# Power.net
KiCad netlist of a schematic drawn in Altium Designer
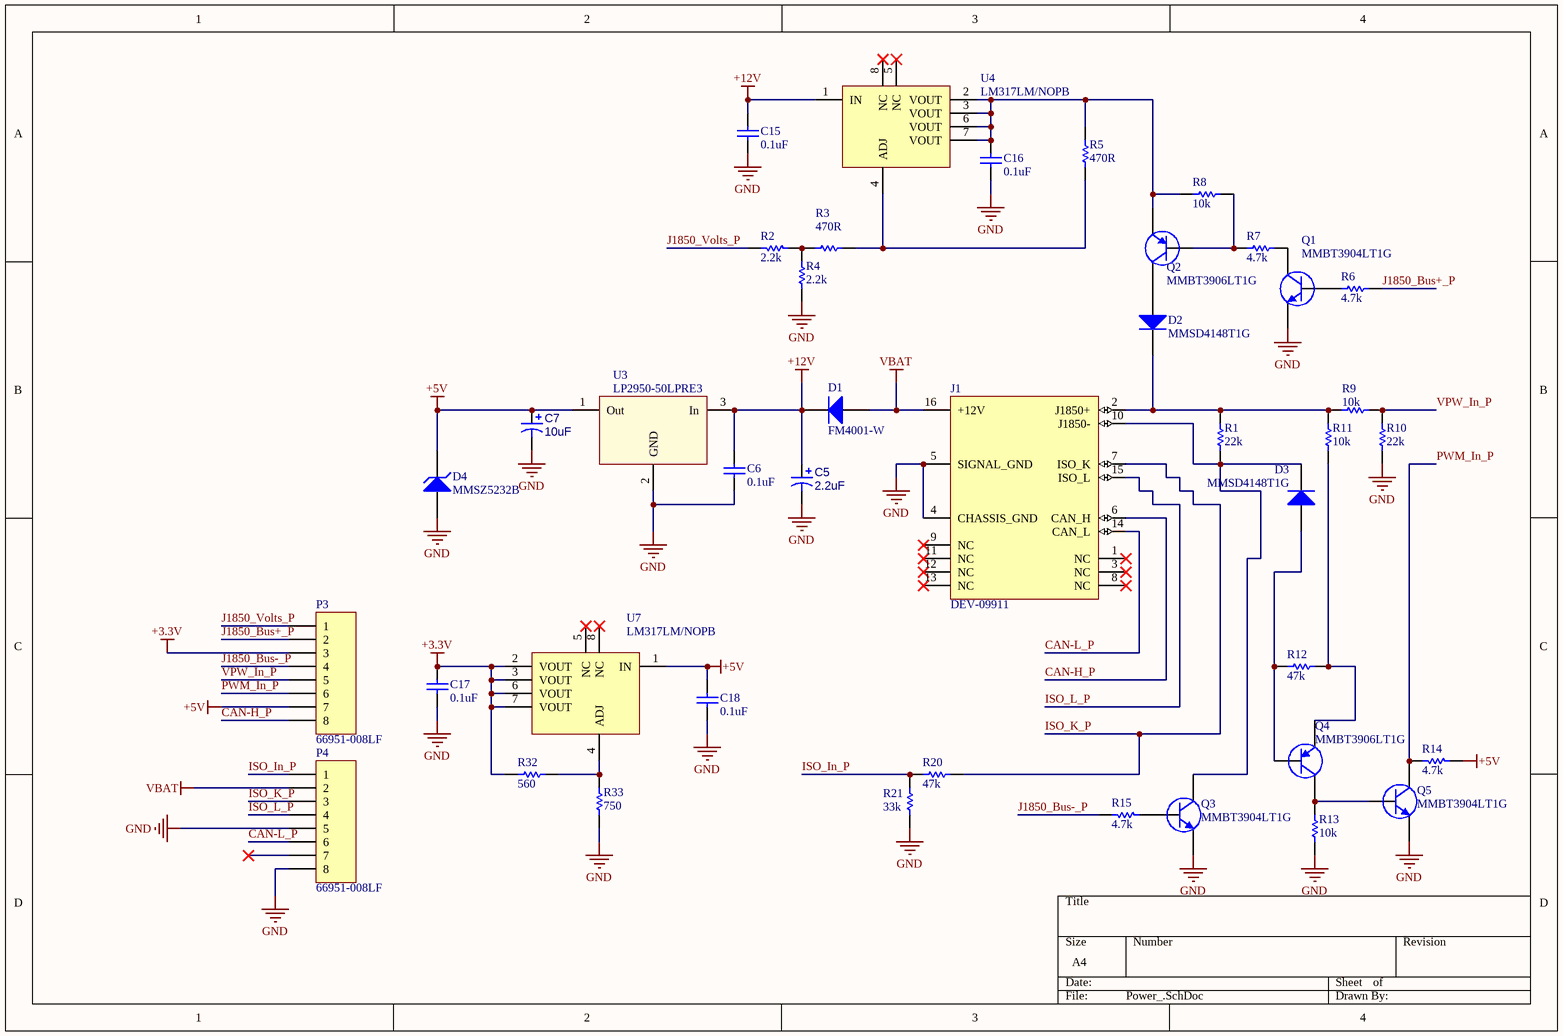
[diagram p0: Power_.SchDoc]

(export (version "E")
  (design (tool "Eeschema 10.0.6"))
  (components
    (comp (ref "C5")
      (value "2.2uF")
      (footprint "Panasonic_Ñ")
      (description "CAP ELECT 2.2UF SV 50V SMD")
      (fields (field (name "MANUFACTURER") "Panasonic") (field (name "PARTNUMBER") "EEE-1HA2R2NR"))
      (libsource (lib "OBDII-components") (part "EEE-1HA2R2NR"))
    )
    (comp (ref "C6")
      (value "0.1uF")
      (footprint "1608[0603]")
      (description "Surface-Mount Ceramic Multilayer Capacitor, 0.1uF, 10% Tolerance, 0603 Size, 50V")
      (libsource (lib "OBDII-components") (part "C0603C104K5RACTU"))
    )
    (comp (ref "C7")
      (value "10uF")
      (footprint "Panasonic_B")
      (description "CAP ELECT 10UF SV 10V SMD")
      (fields (field (name "MANUFACTURER") "Panasonic") (field (name "PARTNUMBER") "EEE-1AA100NR"))
      (libsource (lib "OBDII-components") (part "EEE-1AA100NR"))
    )
    (comp (ref "C15")
      (value "0.1uF")
      (footprint "1608[0603]")
      (description "Surface-Mount Ceramic Multilayer Capacitor, 0.1uF, X7R, 10% Tolerance, 0603 Size, 25V")
      (fields (field (name "PUBLISHER") "Altium Limited"))
      (libsource (lib "OBDII-components") (part "CGA3E2X7R1E104K080AA"))
    )
    (comp (ref "C16")
      (value "0.1uF")
      (footprint "1608[0603]")
      (description "Surface-Mount Ceramic Multilayer Capacitor, 0.1uF, X7R, 10% Tolerance, 0603 Size, 25V")
      (fields (field (name "PUBLISHER") "Altium Limited"))
      (libsource (lib "OBDII-components") (part "CGA3E2X7R1E104K080AA"))
    )
    (comp (ref "C17")
      (value "0.1uF")
      (footprint "1608[0603]")
      (description "Surface-Mount Ceramic Multilayer Capacitor, 0.1uF, 10% Tolerance, 0603 Size, 50V")
      (libsource (lib "OBDII-components") (part "C0603C104K5RACTU"))
    )
    (comp (ref "C18")
      (value "0.1uF")
      (footprint "1608[0603]")
      (description "Surface-Mount Ceramic Multilayer Capacitor, 0.1uF, 10% Tolerance, 0603 Size, 50V")
      (libsource (lib "OBDII-components") (part "C0603C104K5RACTU"))
    )
    (comp (ref "D1")
      (value "FM4001-W")
      (footprint "SMA,2.8mm")
      (description "1 Amp 50V  Rectifier")
      (libsource (lib "OBDII-components") (part "FM4001-W"))
    )
    (comp (ref "D2")
      (value "MMSD4148T1G")
      (footprint "SOD123")
      (description "High Conductance Fast Diode")
      (fields
        (field (name "MANUFACTURER") "OnSemi")
        (field (name "PUBLISHER") "Vanteon")
        (field (name "APPROVED") "M. Jablonski")
      )
      (libsource (lib "OBDII-components") (part "MMSD4148T1G"))
    )
    (comp (ref "D3")
      (value "MMSD4148T1G")
      (footprint "SOD123")
      (description "High Conductance Fast Diode")
      (fields
        (field (name "MANUFACTURER") "OnSemi")
        (field (name "PUBLISHER") "Vanteon")
        (field (name "APPROVED") "M. Jablonski")
      )
      (libsource (lib "OBDII-components") (part "MMSD4148T1G"))
    )
    (comp (ref "D4")
      (value "MMSZ5232B")
      (footprint "SOD123")
      (description "Zener Diodes 5.6 Volt 0.5W 5%")
      (libsource (lib "OBDII-components") (part "MMSZ5232B"))
    )
    (comp (ref "J1")
      (value "DEV-09911")
      (footprint "DEV-09911 - II")
      (description "OBD-II Connector")
      (fields (field (name "MANUFACTURER") "SparkFun Electronics"))
      (libsource (lib "OBDII-components") (part "OBDII_DEV-09911"))
    )
    (comp (ref "P3")
      (value "66951-008LF")
      (footprint "HDR1X8")
      (description "Connector, 8-Pin, 2.54 pitch, 1 row")
      (fields (field (name "PUBLISHER") "Altium Limited"))
      (libsource (lib "OBDII-components") (part "66951-008LF"))
    )
    (comp (ref "P4")
      (value "66951-008LF")
      (footprint "HDR1X8")
      (description "Connector, 8-Pin, 2.54 pitch, 1 row")
      (fields (field (name "PUBLISHER") "Altium Limited"))
      (libsource (lib "OBDII-components") (part "66951-008LF"))
    )
    (comp (ref "Q1")
      (value "MMBT3904LT1G")
      (footprint "SOT23")
      (description "NPN 3904 General Purpose Amplifier")
      (fields
        (field (name "MANUFACTURER") "ON Semiconductor")
        (field (name "PUBLISHER") "Vanteon")
        (field (name "APPROVED") "Yes by Implemenation")
      )
      (libsource (lib "OBDII-components") (part "MMBT3904L"))
    )
    (comp (ref "Q2")
      (value "MMBT3906LT1G")
      (footprint "SOT23")
      (description "PNP 3906 General Purpose Amplifier")
      (fields
        (field (name "MANUFACTURER") "ON Semiconductor")
        (field (name "PUBLISHER") "Vanteon")
        (field (name "APPROVED") "Yes by Implemenation")
      )
      (libsource (lib "OBDII-components") (part "MMBT3906L"))
    )
    (comp (ref "Q3")
      (value "MMBT3904LT1G")
      (footprint "SOT23")
      (description "NPN 3904 General Purpose Amplifier")
      (fields
        (field (name "MANUFACTURER") "ON Semiconductor")
        (field (name "PUBLISHER") "Vanteon")
        (field (name "APPROVED") "Yes by Implemenation")
      )
      (libsource (lib "OBDII-components") (part "MMBT3904L"))
    )
    (comp (ref "Q4")
      (value "MMBT3906LT1G")
      (footprint "SOT23")
      (description "PNP 3906 General Purpose Amplifier")
      (fields
        (field (name "MANUFACTURER") "ON Semiconductor")
        (field (name "PUBLISHER") "Vanteon")
        (field (name "APPROVED") "Yes by Implemenation")
      )
      (libsource (lib "OBDII-components") (part "MMBT3906L"))
    )
    (comp (ref "Q5")
      (value "MMBT3904LT1G")
      (footprint "SOT23")
      (description "NPN 3904 General Purpose Amplifier")
      (fields
        (field (name "MANUFACTURER") "ON Semiconductor")
        (field (name "PUBLISHER") "Vanteon")
        (field (name "APPROVED") "Yes by Implemenation")
      )
      (libsource (lib "OBDII-components") (part "MMBT3904L"))
    )
    (comp (ref "R1")
      (value "22k")
      (footprint "ERA-0805")
      (description "Rectangular Thick Film Chip Resistor, 22 kOhm, 0.1% Tolerance, 0805 Size, 0.125 W")
      (libsource (lib "OBDII-components") (part "ERA6AEB223V"))
    )
    (comp (ref "R2")
      (value "2.2k")
      (footprint "ERA-0805")
      (description "Rectangular Thick Film Chip Resistor, 2.2 kOhm, 0.1% Tolerance, 0805 Size, 0.125 W")
      (libsource (lib "OBDII-components") (part "ERA6AEB222V"))
    )
    (comp (ref "R3")
      (value "470R")
      (footprint "ERA-0805")
      (description "Rectangular Thick Film Chip Resistor, 470 Ohm, 0.1% Tolerance, 0805 Size, 0.125 W")
      (libsource (lib "OBDII-components") (part "ERA6AEB471V"))
    )
    (comp (ref "R4")
      (value "2.2k")
      (footprint "ERA-0805")
      (description "Rectangular Thick Film Chip Resistor, 2.2 kOhm, 0.1% Tolerance, 0805 Size, 0.125 W")
      (libsource (lib "OBDII-components") (part "ERA6AEB222V"))
    )
    (comp (ref "R5")
      (value "470R")
      (footprint "ERA-0805")
      (description "Rectangular Thick Film Chip Resistor, 470 Ohm, 0.1% Tolerance, 0805 Size, 0.125 W")
      (libsource (lib "OBDII-components") (part "ERA6AEB471V"))
    )
    (comp (ref "R6")
      (value "4.7k")
      (footprint "ERA-0805")
      (description "Rectangular Thick Film Chip Resistor, 4.7 kOhm, 0.1% Tolerance, 0805 Size, 0.125 W")
      (libsource (lib "OBDII-components") (part "ERA6AEB472V"))
    )
    (comp (ref "R7")
      (value "4.7k")
      (footprint "ERA-0805")
      (description "Rectangular Thick Film Chip Resistor, 4.7 kOhm, 0.1% Tolerance, 0805 Size, 0.125 W")
      (libsource (lib "OBDII-components") (part "ERA6AEB472V"))
    )
    (comp (ref "R8")
      (value "10k")
      (footprint "ERA-0805")
      (description "Rectangular Thick Film Chip Resistor, 10 kOhm, 0.1% Tolerance, 0805 Size, 0.125 W")
      (libsource (lib "OBDII-components") (part "ERA6AEB103V"))
    )
    (comp (ref "R9")
      (value "10k")
      (footprint "ERA-0805")
      (description "Rectangular Thick Film Chip Resistor, 10 kOhm, 0.1% Tolerance, 0805 Size, 0.125 W")
      (libsource (lib "OBDII-components") (part "ERA6AEB103V"))
    )
    (comp (ref "R10")
      (value "22k")
      (footprint "ERA-0805")
      (description "Rectangular Thick Film Chip Resistor, 22 kOhm, 0.1% Tolerance, 0805 Size, 0.125 W")
      (libsource (lib "OBDII-components") (part "ERA6AEB223V"))
    )
    (comp (ref "R11")
      (value "10k")
      (footprint "ERA-0805")
      (description "Rectangular Thick Film Chip Resistor, 10 kOhm, 0.1% Tolerance, 0805 Size, 0.125 W")
      (libsource (lib "OBDII-components") (part "ERA6AEB103V"))
    )
    (comp (ref "R12")
      (value "47k")
      (footprint "ERA-0805")
      (description "Rectangular Thick Film Chip Resistor, 47 kOhm, 0.1% Tolerance, 0805 Size, 0.125 W")
      (libsource (lib "OBDII-components") (part "ERA6AEB473V"))
    )
    (comp (ref "R13")
      (value "10k")
      (footprint "ERA-0805")
      (description "Rectangular Thick Film Chip Resistor, 10 kOhm, 0.1% Tolerance, 0805 Size, 0.125 W")
      (libsource (lib "OBDII-components") (part "ERA6AEB103V"))
    )
    (comp (ref "R14")
      (value "4.7k")
      (footprint "ERA-0805")
      (description "Rectangular Thick Film Chip Resistor, 4.7 kOhm, 0.1% Tolerance, 0805 Size, 0.125 W")
      (libsource (lib "OBDII-components") (part "ERA6AEB472V"))
    )
    (comp (ref "R15")
      (value "4.7k")
      (footprint "ERA-0805")
      (description "Rectangular Thick Film Chip Resistor, 4.7 kOhm, 0.1% Tolerance, 0805 Size, 0.125 W")
      (libsource (lib "OBDII-components") (part "ERA6AEB472V"))
    )
    (comp (ref "R20")
      (value "47k")
      (footprint "ERA-0805")
      (description "Rectangular Thick Film Chip Resistor, 47 kOhm, 0.1% Tolerance, 0805 Size, 0.125 W")
      (libsource (lib "OBDII-components") (part "ERA6AEB473V"))
    )
    (comp (ref "R21")
      (value "33k")
      (footprint "ERA-0805")
      (description "Rectangular Thick Film Chip Resistor, 33 kOhm, 0.1% Tolerance, 0805 Size, 0.125 W")
      (libsource (lib "OBDII-components") (part "ERA6AEB333V"))
    )
    (comp (ref "R32")
      (value "560")
      (footprint "ERA-0805")
      (description "Rectangular Thick Film Chip Resistor, 560 Ohm, 1% Tolerance, 0805 Size, 0.125 W")
      (libsource (lib "OBDII-components") (part "ERJ6ENF5600V"))
    )
    (comp (ref "R33")
      (value "750")
      (footprint "ERA-0805")
      (description "Rectangular Thick Film Chip Resistor, 750 Ohm, 1% Tolerance, 0805 Size, 0.125 W")
      (libsource (lib "OBDII-components") (part "ERJ6ENF7500V"))
    )
    (comp (ref "U3")
      (value "LP2950-50LPRE3")
      (footprint "TO-92 - II")
      (description "Adjustable Micropower Voltage Regulator With Shutdown; 5V; 100 mA")
      (libsource (lib "OBDII-components") (part "LP2950-50LPRE3"))
    )
    (comp (ref "U4")
      (value "LM317LM/NOPB")
      (footprint "SOIC8N")
      (description "3-terminal adjustable regulator in SO8")
      (fields
        (field (name "MANUFACTURER") "National Semiconductor")
        (field (name "PUBLISHER") "Vanteon")
        (field (name "APPROVED") "Yes by Implementation")
      )
      (libsource (lib "") (part "LM317LM_1"))
    )
    (comp (ref "U7")
      (value "LM317LM/NOPB")
      (footprint "SOIC8N")
      (description "3-terminal adjustable regulator in SO8")
      (fields
        (field (name "MANUFACTURER") "National Semiconductor")
        (field (name "PUBLISHER") "Vanteon")
        (field (name "APPROVED") "Yes by Implementation")
      )
      (libsource (lib "OBDII-components") (part "LM317LM"))
    )
  )
  (nets
    (net (code "1") (name "+3.3V") (class "Default")
      (node (ref "C17") (pin "2") (pinfunction "2_2") (pintype "passive"))
      (node (ref "P3") (pin "3") (pinfunction "3_3") (pintype "passive"))
      (node (ref "R32") (pin "1") (pinfunction "1_1") (pintype "passive"))
      (node (ref "U7") (pin "2") (pinfunction "VOUT_2") (pintype "passive"))
      (node (ref "U7") (pin "3") (pinfunction "VOUT_3") (pintype "passive"))
      (node (ref "U7") (pin "6") (pinfunction "VOUT_6") (pintype "passive"))
      (node (ref "U7") (pin "7") (pinfunction "VOUT_7") (pintype "passive"))
    )
    (net (code "2") (name "+5V") (class "Default")
      (node (ref "C18") (pin "2") (pinfunction "2_2") (pintype "passive"))
      (node (ref "C7") (pin "1") (pinfunction "1_1") (pintype "passive"))
      (node (ref "D4") (pin "1") (pinfunction "K_1") (pintype "passive"))
      (node (ref "P3") (pin "7") (pinfunction "7_7") (pintype "passive"))
      (node (ref "R14") (pin "1") (pinfunction "1_1") (pintype "passive"))
      (node (ref "U3") (pin "1") (pinfunction "Out_1") (pintype "power_in"))
      (node (ref "U7") (pin "1") (pinfunction "IN_1") (pintype "power_in"))
    )
    (net (code "3") (name "+12V") (class "Default")
      (node (ref "C15") (pin "2") (pinfunction "2_2") (pintype "passive"))
      (node (ref "C5") (pin "1") (pinfunction "1_1") (pintype "passive"))
      (node (ref "C6") (pin "2") (pinfunction "2_2") (pintype "passive"))
      (node (ref "D1") (pin "2") (pinfunction "K_2") (pintype "passive"))
      (node (ref "U3") (pin "3") (pinfunction "In_3") (pintype "power_in"))
      (node (ref "U4") (pin "1") (pinfunction "IN_1") (pintype "power_in"))
    )
    (net (code "4") (name "/CAN-H_P") (class "Default")
      (node (ref "J1") (pin "6") (pinfunction "CAN_H_6") (pintype "bidirectional"))
      (node (ref "P3") (pin "8") (pinfunction "8_8") (pintype "passive"))
    )
    (net (code "5") (name "/CAN-L_P") (class "Default")
      (node (ref "J1") (pin "14") (pinfunction "CAN_L_14") (pintype "bidirectional"))
      (node (ref "P4") (pin "6") (pinfunction "6_6") (pintype "passive"))
    )
    (net (code "6") (name "/ISO_In_P") (class "Default")
      (node (ref "P4") (pin "1") (pinfunction "1_1") (pintype "passive"))
      (node (ref "R20") (pin "1") (pinfunction "1_1") (pintype "passive"))
      (node (ref "R21") (pin "2") (pinfunction "2_2") (pintype "passive"))
    )
    (net (code "7") (name "/ISO_K_P") (class "Default")
      (node (ref "J1") (pin "7") (pinfunction "ISO_K_7") (pintype "bidirectional"))
      (node (ref "P4") (pin "3") (pinfunction "3_3") (pintype "passive"))
      (node (ref "R20") (pin "2") (pinfunction "2_2") (pintype "passive"))
    )
    (net (code "8") (name "/ISO_L_P") (class "Default")
      (node (ref "J1") (pin "15") (pinfunction "ISO_L_15") (pintype "bidirectional"))
      (node (ref "P4") (pin "4") (pinfunction "4_4") (pintype "passive"))
    )
    (net (code "9") (name "/J1850_Bus+_P") (class "Default")
      (node (ref "P3") (pin "2") (pinfunction "2_2") (pintype "passive"))
      (node (ref "R6") (pin "2") (pinfunction "2_2") (pintype "passive"))
    )
    (net (code "10") (name "/J1850_Bus-_P") (class "Default")
      (node (ref "P3") (pin "4") (pinfunction "4_4") (pintype "passive"))
      (node (ref "R15") (pin "2") (pinfunction "2_2") (pintype "passive"))
    )
    (net (code "11") (name "/J1850_Volts_P") (class "Default")
      (node (ref "P3") (pin "1") (pinfunction "1_1") (pintype "passive"))
      (node (ref "R2") (pin "2") (pinfunction "2_2") (pintype "passive"))
    )
    (net (code "12") (name "/PWM_In_P") (class "Default")
      (node (ref "P3") (pin "6") (pinfunction "6_6") (pintype "passive"))
      (node (ref "Q5") (pin "3") (pinfunction "C_3") (pintype "passive"))
      (node (ref "R14") (pin "2") (pinfunction "2_2") (pintype "passive"))
    )
    (net (code "13") (name "/VPW_In_P") (class "Default")
      (node (ref "P3") (pin "5") (pinfunction "5_5") (pintype "passive"))
      (node (ref "R10") (pin "2") (pinfunction "2_2") (pintype "passive"))
      (node (ref "R9") (pin "1") (pinfunction "1_1") (pintype "passive"))
    )
    (net (code "14") (name "GND") (class "Default")
      (node (ref "C15") (pin "1") (pinfunction "1_1") (pintype "passive"))
      (node (ref "C16") (pin "1") (pinfunction "1_1") (pintype "passive"))
      (node (ref "C17") (pin "1") (pinfunction "1_1") (pintype "passive"))
      (node (ref "C18") (pin "1") (pinfunction "1_1") (pintype "passive"))
      (node (ref "C5") (pin "2") (pinfunction "2_2") (pintype "passive"))
      (node (ref "C6") (pin "1") (pinfunction "1_1") (pintype "passive"))
      (node (ref "C7") (pin "2") (pinfunction "2_2") (pintype "passive"))
      (node (ref "D4") (pin "2") (pinfunction "A_2") (pintype "passive"))
      (node (ref "J1") (pin "4") (pinfunction "CHASSIS_GND_4") (pintype "power_in"))
      (node (ref "J1") (pin "5") (pinfunction "SIGNAL_GND_5") (pintype "power_in"))
      (node (ref "P4") (pin "5") (pinfunction "5_5") (pintype "passive"))
      (node (ref "P4") (pin "8") (pinfunction "8_8") (pintype "passive"))
      (node (ref "Q1") (pin "2") (pinfunction "E_2") (pintype "passive"))
      (node (ref "Q3") (pin "2") (pinfunction "E_2") (pintype "passive"))
      (node (ref "Q5") (pin "2") (pinfunction "E_2") (pintype "passive"))
      (node (ref "R10") (pin "1") (pinfunction "1_1") (pintype "passive"))
      (node (ref "R13") (pin "2") (pinfunction "2_2") (pintype "passive"))
      (node (ref "R21") (pin "1") (pinfunction "1_1") (pintype "passive"))
      (node (ref "R33") (pin "1") (pinfunction "1_1") (pintype "passive"))
      (node (ref "R4") (pin "1") (pinfunction "1_1") (pintype "passive"))
      (node (ref "U3") (pin "2") (pinfunction "GND_2") (pintype "power_in"))
    )
    (net (code "15") (name "Net-(D2-A)") (class "Default")
      (node (ref "D2") (pin "1") (pinfunction "A_1") (pintype "passive"))
      (node (ref "Q2") (pin "3") (pinfunction "C_3") (pintype "passive"))
    )
    (net (code "16") (name "Net-(D2-C)") (class "Default")
      (node (ref "D2") (pin "2") (pinfunction "C_2") (pintype "passive"))
      (node (ref "J1") (pin "2") (pinfunction "J1850+_2") (pintype "bidirectional"))
      (node (ref "R1") (pin "2") (pinfunction "2_2") (pintype "passive"))
      (node (ref "R11") (pin "1") (pinfunction "1_1") (pintype "passive"))
      (node (ref "R9") (pin "2") (pinfunction "2_2") (pintype "passive"))
    )
    (net (code "17") (name "Net-(D3-A)") (class "Default")
      (node (ref "D3") (pin "1") (pinfunction "A_1") (pintype "passive"))
      (node (ref "Q4") (pin "1") (pinfunction "B_1") (pintype "passive"))
      (node (ref "R12") (pin "1") (pinfunction "1_1") (pintype "passive"))
    )
    (net (code "18") (name "Net-(D3-C)") (class "Default")
      (node (ref "D3") (pin "2") (pinfunction "C_2") (pintype "passive"))
      (node (ref "J1") (pin "10") (pinfunction "J1850-_10") (pintype "bidirectional"))
      (node (ref "Q3") (pin "3") (pinfunction "C_3") (pintype "passive"))
      (node (ref "R1") (pin "1") (pinfunction "1_1") (pintype "passive"))
    )
    (net (code "19") (name "Net-(Q1-B)") (class "Default")
      (node (ref "Q1") (pin "1") (pinfunction "B_1") (pintype "passive"))
      (node (ref "R6") (pin "1") (pinfunction "1_1") (pintype "passive"))
    )
    (net (code "20") (name "Net-(Q1-C)") (class "Default")
      (node (ref "Q1") (pin "3") (pinfunction "C_3") (pintype "passive"))
      (node (ref "R7") (pin "2") (pinfunction "2_2") (pintype "passive"))
    )
    (net (code "21") (name "Net-(Q2-B)") (class "Default")
      (node (ref "Q2") (pin "1") (pinfunction "B_1") (pintype "passive"))
      (node (ref "R7") (pin "1") (pinfunction "1_1") (pintype "passive"))
      (node (ref "R8") (pin "1") (pinfunction "1_1") (pintype "passive"))
    )
    (net (code "22") (name "Net-(Q2-E)") (class "Default")
      (node (ref "C16") (pin "2") (pinfunction "2_2") (pintype "passive"))
      (node (ref "Q2") (pin "2") (pinfunction "E_2") (pintype "passive"))
      (node (ref "R5") (pin "2") (pinfunction "2_2") (pintype "passive"))
      (node (ref "R8") (pin "2") (pinfunction "2_2") (pintype "passive"))
      (node (ref "U4") (pin "2") (pinfunction "VOUT_2") (pintype "passive"))
      (node (ref "U4") (pin "3") (pinfunction "VOUT_3") (pintype "passive"))
      (node (ref "U4") (pin "6") (pinfunction "VOUT_6") (pintype "passive"))
      (node (ref "U4") (pin "7") (pinfunction "VOUT_7") (pintype "passive"))
    )
    (net (code "23") (name "Net-(Q3-B)") (class "Default")
      (node (ref "Q3") (pin "1") (pinfunction "B_1") (pintype "passive"))
      (node (ref "R15") (pin "1") (pinfunction "1_1") (pintype "passive"))
    )
    (net (code "24") (name "Net-(Q4-C)") (class "Default")
      (node (ref "Q4") (pin "3") (pinfunction "C_3") (pintype "passive"))
      (node (ref "Q5") (pin "1") (pinfunction "B_1") (pintype "passive"))
      (node (ref "R13") (pin "1") (pinfunction "1_1") (pintype "passive"))
    )
    (net (code "25") (name "Net-(Q4-E)") (class "Default")
      (node (ref "Q4") (pin "2") (pinfunction "E_2") (pintype "passive"))
      (node (ref "R11") (pin "2") (pinfunction "2_2") (pintype "passive"))
      (node (ref "R12") (pin "2") (pinfunction "2_2") (pintype "passive"))
    )
    (net (code "26") (name "Net-(R2-Pad1)") (class "Default")
      (node (ref "R2") (pin "1") (pinfunction "1_1") (pintype "passive"))
      (node (ref "R3") (pin "2") (pinfunction "2_2") (pintype "passive"))
      (node (ref "R4") (pin "2") (pinfunction "2_2") (pintype "passive"))
    )
    (net (code "27") (name "Net-(U4-ADJ)") (class "Default")
      (node (ref "R3") (pin "1") (pinfunction "1_1") (pintype "passive"))
      (node (ref "R5") (pin "1") (pinfunction "1_1") (pintype "passive"))
      (node (ref "U4") (pin "4") (pinfunction "ADJ_4") (pintype "power_in"))
    )
    (net (code "28") (name "Net-(U7-ADJ)") (class "Default")
      (node (ref "R32") (pin "2") (pinfunction "2_2") (pintype "passive"))
      (node (ref "R33") (pin "2") (pinfunction "2_2") (pintype "passive"))
      (node (ref "U7") (pin "4") (pinfunction "ADJ_4") (pintype "power_in"))
    )
    (net (code "29") (name "VBAT") (class "Default")
      (node (ref "D1") (pin "1") (pinfunction "A_1") (pintype "passive"))
      (node (ref "J1") (pin "16") (pinfunction "+12V_16") (pintype "power_in"))
      (node (ref "P4") (pin "2") (pinfunction "2_2") (pintype "passive"))
    )
    (net (code "30") (name "unconnected-(J1-NC-Pad1)") (class "Default")
      (node (ref "J1") (pin "1") (pinfunction "NC_1") (pintype "passive+no_connect"))
    )
    (net (code "31") (name "unconnected-(J1-NC-Pad3)") (class "Default")
      (node (ref "J1") (pin "3") (pinfunction "NC_3") (pintype "passive+no_connect"))
    )
    (net (code "32") (name "unconnected-(J1-NC-Pad8)") (class "Default")
      (node (ref "J1") (pin "8") (pinfunction "NC_8") (pintype "passive+no_connect"))
    )
    (net (code "33") (name "unconnected-(J1-NC-Pad9)") (class "Default")
      (node (ref "J1") (pin "9") (pinfunction "NC_9") (pintype "passive+no_connect"))
    )
    (net (code "34") (name "unconnected-(J1-NC-Pad11)") (class "Default")
      (node (ref "J1") (pin "11") (pinfunction "NC_11") (pintype "passive+no_connect"))
    )
    (net (code "35") (name "unconnected-(J1-NC-Pad12)") (class "Default")
      (node (ref "J1") (pin "12") (pinfunction "NC_12") (pintype "passive+no_connect"))
    )
    (net (code "36") (name "unconnected-(J1-NC-Pad13)") (class "Default")
      (node (ref "J1") (pin "13") (pinfunction "NC_13") (pintype "passive+no_connect"))
    )
    (net (code "37") (name "unconnected-(P4-Pad7)") (class "Default")
      (node (ref "P4") (pin "7") (pinfunction "7_7") (pintype "passive+no_connect"))
    )
    (net (code "38") (name "unconnected-(U4-NC-Pad5)") (class "Default")
      (node (ref "U4") (pin "5") (pinfunction "NC_5") (pintype "passive+no_connect"))
    )
    (net (code "39") (name "unconnected-(U4-NC-Pad8)") (class "Default")
      (node (ref "U4") (pin "8") (pinfunction "NC_8") (pintype "passive+no_connect"))
    )
    (net (code "40") (name "unconnected-(U7-NC-Pad5)") (class "Default")
      (node (ref "U7") (pin "5") (pinfunction "NC_5") (pintype "passive+no_connect"))
    )
    (net (code "41") (name "unconnected-(U7-NC-Pad8)") (class "Default")
      (node (ref "U7") (pin "8") (pinfunction "NC_8") (pintype "passive+no_connect"))
    )
  )
)
